# CC2530-Module.net
KiCad netlist of a schematic drawn in Altium Designer
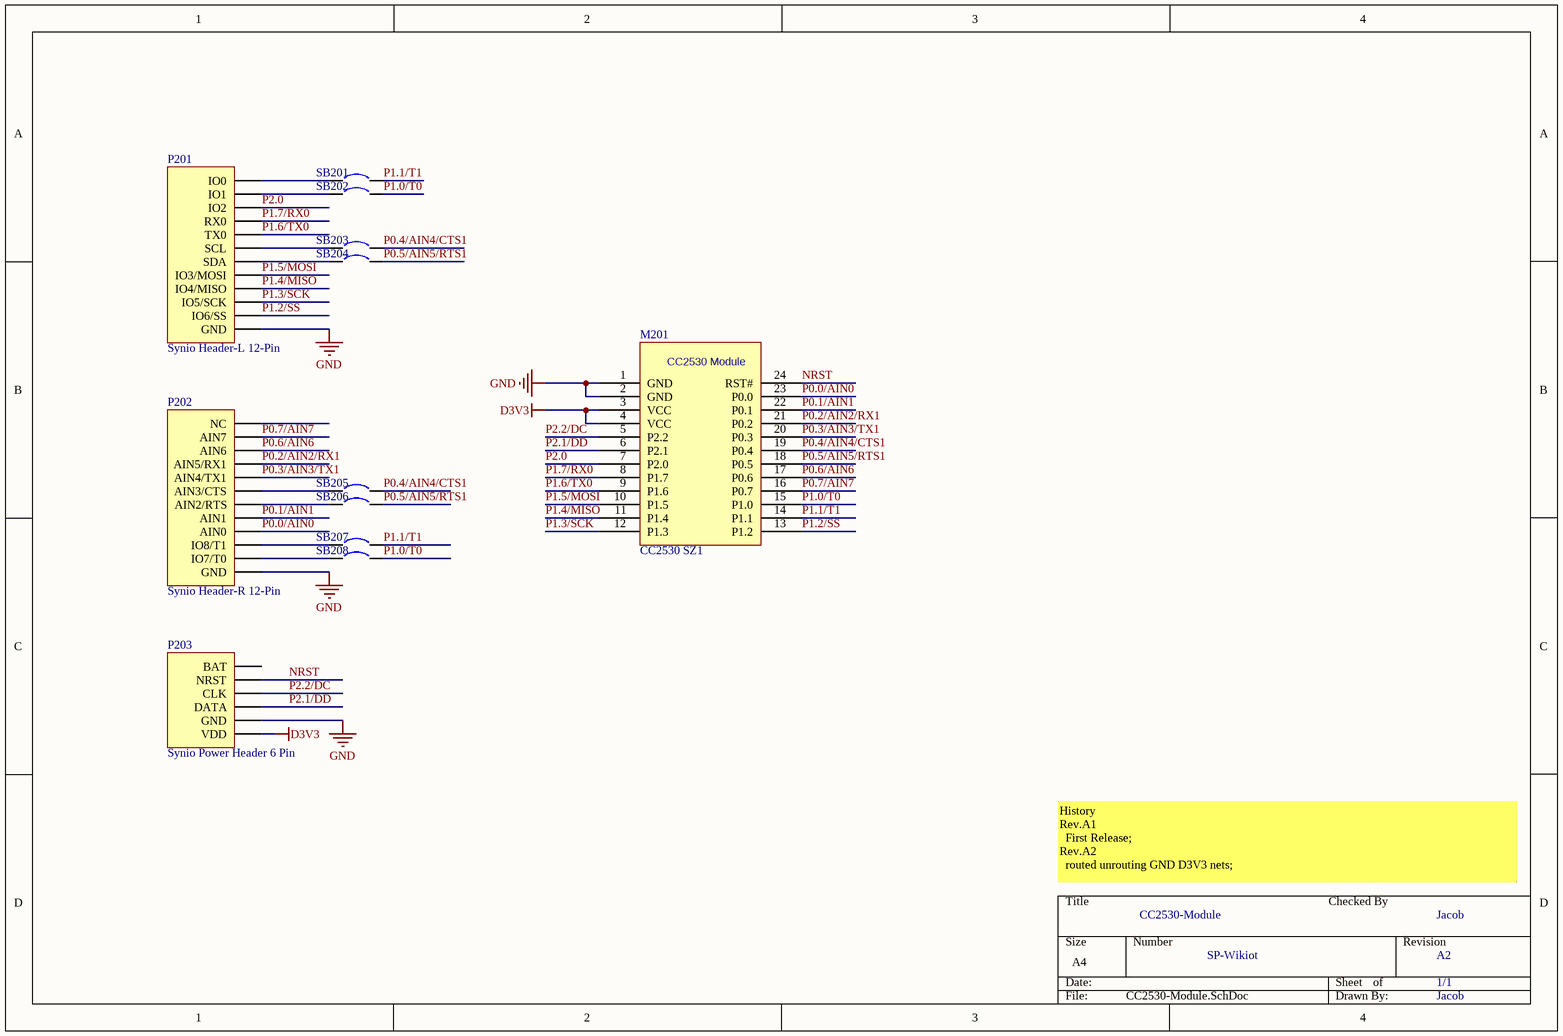
[diagram p0: CC2530-Module.SchDoc]

(export (version "E")
  (design (tool "Eeschema 10.0.6"))
  (components
    (comp (ref "M201")
      (value "CC2530 SZ1")
      (footprint "CC2530-SMT")
      (description "CC2530 SZ1 Module")
      (libsource (lib "Module") (part "CC2530 SZ1"))
    )
    (comp (ref "P201")
      (value "Synio Header-L 12-Pin")
      (footprint "HDR1X12")
      (description "Synio Header-L, 12-Pin")
      (fields (field (name "PUBLISHER") "Altium Limited"))
      (libsource (lib "Connector") (part "Synio Header-L 12-Pin"))
    )
    (comp (ref "P202")
      (value "Synio Header-R 12-Pin")
      (footprint "HDR1X12")
      (description "Synio Header-R, 12-Pin")
      (fields (field (name "PUBLISHER") "Altium Limited"))
      (libsource (lib "Connector") (part "Synio Header-R 12-Pin"))
    )
    (comp (ref "P203")
      (value "Synio Power Header 6 Pin")
      (footprint "HDR1X6/2.54MM")
      (libsource (lib "Connector") (part "Synio Power Header 6 Pin"))
    )
    (comp (ref "SB201")
      (value "Circuit Breaker")
      (footprint "JP2_SMD")
      (fields (field (name "PUBLISHER") "Altium Limited"))
      (libsource (lib "Misc") (part "Circuit Breaker"))
    )
    (comp (ref "SB202")
      (value "Circuit Breaker")
      (footprint "JP2_SMD")
      (fields (field (name "PUBLISHER") "Altium Limited"))
      (libsource (lib "Misc") (part "Circuit Breaker"))
    )
    (comp (ref "SB203")
      (value "Circuit Breaker")
      (footprint "JP2_SMD")
      (fields (field (name "PUBLISHER") "Altium Limited"))
      (libsource (lib "Misc") (part "Circuit Breaker"))
    )
    (comp (ref "SB204")
      (value "Circuit Breaker")
      (footprint "JP2_SMD")
      (fields (field (name "PUBLISHER") "Altium Limited"))
      (libsource (lib "Misc") (part "Circuit Breaker"))
    )
    (comp (ref "SB205")
      (value "Circuit Breaker")
      (footprint "JP2_SMD")
      (fields (field (name "PUBLISHER") "Altium Limited"))
      (libsource (lib "Misc") (part "Circuit Breaker"))
    )
    (comp (ref "SB206")
      (value "Circuit Breaker")
      (footprint "JP2_SMD")
      (fields (field (name "PUBLISHER") "Altium Limited"))
      (libsource (lib "Misc") (part "Circuit Breaker"))
    )
    (comp (ref "SB207")
      (value "Circuit Breaker")
      (footprint "JP2_SMD")
      (fields (field (name "PUBLISHER") "Altium Limited"))
      (libsource (lib "Misc") (part "Circuit Breaker"))
    )
    (comp (ref "SB208")
      (value "Circuit Breaker")
      (footprint "JP2_SMD")
      (fields (field (name "PUBLISHER") "Altium Limited"))
      (libsource (lib "Misc") (part "Circuit Breaker"))
    )
  )
  (nets
    (net (code "1") (name "/NRST") (class "Default")
      (node (ref "M201") (pin "24") (pinfunction "RST#_24") (pintype "passive"))
      (node (ref "P203") (pin "5") (pinfunction "NRST_5") (pintype "passive"))
    )
    (net (code "2") (name "/P0.0{slash}AIN0") (class "Default")
      (node (ref "M201") (pin "23") (pinfunction "P0.0_23") (pintype "passive"))
      (node (ref "P202") (pin "4") (pinfunction "AIN0_4") (pintype "passive"))
    )
    (net (code "3") (name "/P0.1{slash}AIN1") (class "Default")
      (node (ref "M201") (pin "22") (pinfunction "P0.1_22") (pintype "passive"))
      (node (ref "P202") (pin "5") (pinfunction "AIN1_5") (pintype "passive"))
    )
    (net (code "4") (name "/P0.2{slash}AIN2{slash}RX1") (class "Default")
      (node (ref "M201") (pin "21") (pinfunction "P0.2_21") (pintype "passive"))
      (node (ref "P202") (pin "9") (pinfunction "AIN5/RX1_9") (pintype "passive"))
    )
    (net (code "5") (name "/P0.3{slash}AIN3{slash}TX1") (class "Default")
      (node (ref "M201") (pin "20") (pinfunction "P0.3_20") (pintype "passive"))
      (node (ref "P202") (pin "8") (pinfunction "AIN4/TX1_8") (pintype "passive"))
    )
    (net (code "6") (name "/P0.4{slash}AIN4{slash}CTS1") (class "Default")
      (node (ref "M201") (pin "19") (pinfunction "P0.4_19") (pintype "passive"))
      (node (ref "SB203") (pin "2") (pinfunction "2_2") (pintype "passive"))
      (node (ref "SB205") (pin "2") (pinfunction "2_2") (pintype "passive"))
    )
    (net (code "7") (name "/P0.5{slash}AIN5{slash}RTS1") (class "Default")
      (node (ref "M201") (pin "18") (pinfunction "P0.5_18") (pintype "passive"))
      (node (ref "SB204") (pin "2") (pinfunction "2_2") (pintype "passive"))
      (node (ref "SB206") (pin "2") (pinfunction "2_2") (pintype "passive"))
    )
    (net (code "8") (name "/P0.6{slash}AIN6") (class "Default")
      (node (ref "M201") (pin "17") (pinfunction "P0.6_17") (pintype "passive"))
      (node (ref "P202") (pin "10") (pinfunction "AIN6_10") (pintype "passive"))
    )
    (net (code "9") (name "/P0.7{slash}AIN7") (class "Default")
      (node (ref "M201") (pin "16") (pinfunction "P0.7_16") (pintype "passive"))
      (node (ref "P202") (pin "11") (pinfunction "AIN7_11") (pintype "passive"))
    )
    (net (code "10") (name "/P1.0{slash}T0") (class "Default")
      (node (ref "M201") (pin "15") (pinfunction "P1.0_15") (pintype "passive"))
      (node (ref "SB202") (pin "2") (pinfunction "2_2") (pintype "passive"))
      (node (ref "SB208") (pin "2") (pinfunction "2_2") (pintype "passive"))
    )
    (net (code "11") (name "/P1.1{slash}T1") (class "Default")
      (node (ref "M201") (pin "14") (pinfunction "P1.1_14") (pintype "passive"))
      (node (ref "SB201") (pin "2") (pinfunction "2_2") (pintype "passive"))
      (node (ref "SB207") (pin "2") (pinfunction "2_2") (pintype "passive"))
    )
    (net (code "12") (name "/P1.2{slash}SS") (class "Default")
      (node (ref "M201") (pin "13") (pinfunction "P1.2_13") (pintype "passive"))
      (node (ref "P201") (pin "2") (pinfunction "IO6/SS_2") (pintype "passive"))
    )
    (net (code "13") (name "/P1.3{slash}SCK") (class "Default")
      (node (ref "M201") (pin "12") (pinfunction "P1.3_12") (pintype "passive"))
      (node (ref "P201") (pin "3") (pinfunction "IO5/SCK_3") (pintype "passive"))
    )
    (net (code "14") (name "/P1.4{slash}MISO") (class "Default")
      (node (ref "M201") (pin "11") (pinfunction "P1.4_11") (pintype "passive"))
      (node (ref "P201") (pin "4") (pinfunction "IO4/MISO_4") (pintype "passive"))
    )
    (net (code "15") (name "/P1.5{slash}MOSI") (class "Default")
      (node (ref "M201") (pin "10") (pinfunction "P1.5_10") (pintype "passive"))
      (node (ref "P201") (pin "5") (pinfunction "IO3/MOSI_5") (pintype "passive"))
    )
    (net (code "16") (name "/P1.6{slash}TX0") (class "Default")
      (node (ref "M201") (pin "9") (pinfunction "P1.6_9") (pintype "passive"))
      (node (ref "P201") (pin "8") (pinfunction "TX0_8") (pintype "passive"))
    )
    (net (code "17") (name "/P1.7{slash}RX0") (class "Default")
      (node (ref "M201") (pin "8") (pinfunction "P1.7_8") (pintype "passive"))
      (node (ref "P201") (pin "9") (pinfunction "RX0_9") (pintype "passive"))
    )
    (net (code "18") (name "/P2.0") (class "Default")
      (node (ref "M201") (pin "7") (pinfunction "P2.0_7") (pintype "passive"))
      (node (ref "P201") (pin "10") (pinfunction "IO2_10") (pintype "passive"))
    )
    (net (code "19") (name "/P2.1{slash}DD") (class "Default")
      (node (ref "M201") (pin "6") (pinfunction "P2.1_6") (pintype "passive"))
      (node (ref "P203") (pin "3") (pinfunction "DATA_3") (pintype "passive"))
    )
    (net (code "20") (name "/P2.2{slash}DC") (class "Default")
      (node (ref "M201") (pin "5") (pinfunction "P2.2_5") (pintype "passive"))
      (node (ref "P203") (pin "4") (pinfunction "CLK_4") (pintype "passive"))
    )
    (net (code "21") (name "D3V3") (class "Default")
      (node (ref "M201") (pin "3") (pinfunction "VCC_3") (pintype "passive"))
      (node (ref "M201") (pin "4") (pinfunction "VCC_4") (pintype "passive"))
      (node (ref "P203") (pin "1") (pinfunction "VDD_1") (pintype "passive"))
    )
    (net (code "22") (name "GND") (class "Default")
      (node (ref "M201") (pin "1") (pinfunction "GND_1") (pintype "passive"))
      (node (ref "M201") (pin "2") (pinfunction "GND_2") (pintype "passive"))
      (node (ref "P201") (pin "1") (pinfunction "GND_1") (pintype "passive"))
      (node (ref "P202") (pin "1") (pinfunction "GND_1") (pintype "passive"))
      (node (ref "P203") (pin "2") (pinfunction "GND_2") (pintype "passive"))
    )
    (net (code "23") (name "Net-(P201-IO0)") (class "Default")
      (node (ref "P201") (pin "12") (pinfunction "IO0_12") (pintype "passive"))
      (node (ref "SB201") (pin "1") (pinfunction "1_1") (pintype "passive"))
    )
    (net (code "24") (name "Net-(P201-IO1)") (class "Default")
      (node (ref "P201") (pin "11") (pinfunction "IO1_11") (pintype "passive"))
      (node (ref "SB202") (pin "1") (pinfunction "1_1") (pintype "passive"))
    )
    (net (code "25") (name "Net-(P201-SCL)") (class "Default")
      (node (ref "P201") (pin "7") (pinfunction "SCL_7") (pintype "passive"))
      (node (ref "SB203") (pin "1") (pinfunction "1_1") (pintype "passive"))
    )
    (net (code "26") (name "Net-(P201-SDA)") (class "Default")
      (node (ref "P201") (pin "6") (pinfunction "SDA_6") (pintype "passive"))
      (node (ref "SB204") (pin "1") (pinfunction "1_1") (pintype "passive"))
    )
    (net (code "27") (name "Net-(P202-AIN2{slash}RTS)") (class "Default")
      (node (ref "P202") (pin "6") (pinfunction "AIN2/RTS_6") (pintype "passive"))
      (node (ref "SB206") (pin "1") (pinfunction "1_1") (pintype "passive"))
    )
    (net (code "28") (name "Net-(P202-AIN3{slash}CTS)") (class "Default")
      (node (ref "P202") (pin "7") (pinfunction "AIN3/CTS_7") (pintype "passive"))
      (node (ref "SB205") (pin "1") (pinfunction "1_1") (pintype "passive"))
    )
    (net (code "29") (name "Net-(P202-IO7{slash}T0)") (class "Default")
      (node (ref "P202") (pin "2") (pinfunction "IO7/T0_2") (pintype "passive"))
      (node (ref "SB208") (pin "1") (pinfunction "1_1") (pintype "passive"))
    )
    (net (code "30") (name "Net-(P202-IO8{slash}T1)") (class "Default")
      (node (ref "P202") (pin "3") (pinfunction "IO8/T1_3") (pintype "passive"))
      (node (ref "SB207") (pin "1") (pinfunction "1_1") (pintype "passive"))
    )
    (net (code "31") (name "unconnected-(P202-NC-Pad12)") (class "Default")
      (node (ref "P202") (pin "12") (pinfunction "NC_12") (pintype "passive"))
    )
    (net (code "32") (name "unconnected-(P203-BAT-Pad6)") (class "Default")
      (node (ref "P203") (pin "6") (pinfunction "BAT_6") (pintype "passive"))
    )
  )
)
